# mqtt_doorbell_v2a.net
KiCad netlist of a schematic drawn in EAGLE
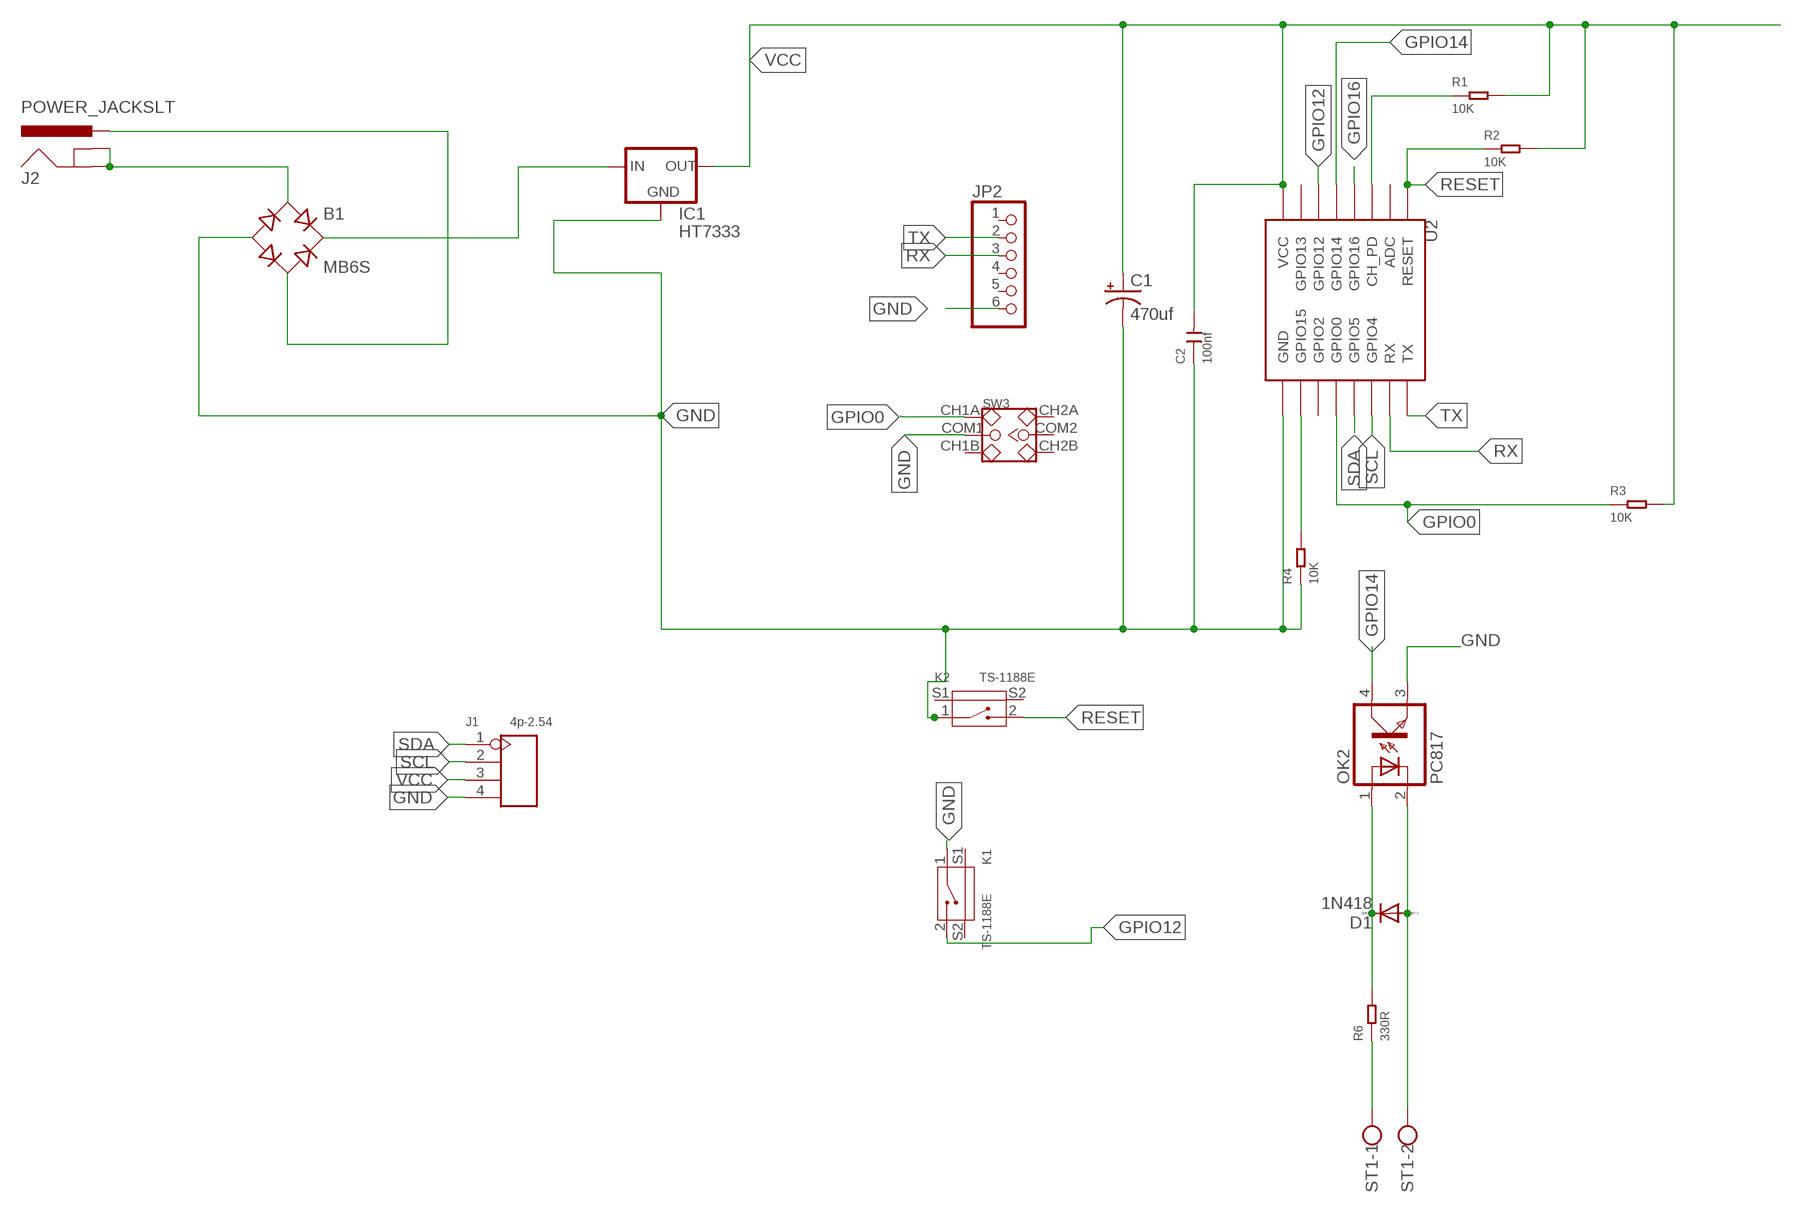
[diagram p0: schematic, sheet 1]

(export (version "E")
  (design (tool "Eeschema 10.0.6"))
  (components
    (comp (ref "B1")
      (value "MB6S")
      (footprint "eagle-import:SOIC-4")
      (libsource (lib "eagle-import") (part "MBS4"))
    )
    (comp (ref "C1")
      (value "470uf")
      (footprint "eagle-import:PANASONIC_D")
      (libsource (lib "eagle-import") (part "47UF-50V-20%(ELECT)"))
    )
    (comp (ref "C2")
      (value "100nf")
      (footprint "eagle-import:C0603")
      (fields (field (name "MPN") "CC0603KRX7R9BB104"))
      (libsource (lib "eagle-import") (part "CERAMIC-100NF-50V-10%-X7R(0603)"))
    )
    (comp (ref "D1")
      (value "1N418")
      (footprint "eagle-import:SOD-123_MINI-SMA")
      (libsource (lib "eagle-import") (part "CGRM400-G1"))
    )
    (comp (ref "IC1")
      (value "HT7333")
      (footprint "eagle-import:SOT-89")
      (libsource (lib "eagle-import") (part "HT7333"))
    )
    (comp (ref "J1")
      (value "4p-2.54")
      (footprint "eagle-import:H4-2.54")
      (fields (field (name "MPN") "F185-1104A1BSYA1"))
      (libsource (lib "eagle-import") (part "DIP-BLACK-FEMALE-HEADER-VERT(4P-2.54)"))
    )
    (comp (ref "J2")
      (value "POWER_JACKSLT")
      (footprint "eagle-import:POWER_JACK_SLOT")
      (libsource (lib "eagle-import") (part "POWER_JACKSLT"))
    )
    (comp (ref "JP2")
      (value "PINHD-1X6")
      (footprint "eagle-import:1X06")
      (libsource (lib "eagle-import") (part "PINHD-1X6"))
    )
    (comp (ref "K1")
      (value "TS-1188E")
      (footprint "eagle-import:SW4-SMD-7.0X3.5X3.5MM-90D")
      (libsource (lib "eagle-import") (part "SMD-BUTTON(2+2P-7X3.5MM-90D)"))
    )
    (comp (ref "K2")
      (value "TS-1188E")
      (footprint "eagle-import:SW4-SMD-7.0X3.5X3.5MM-90D")
      (libsource (lib "eagle-import") (part "SMD-BUTTON(2+2P-7X3.5MM-90D)"))
    )
    (comp (ref "OK2")
      (value "PC817")
      (footprint "eagle-import:SOP-4-2.54")
      (libsource (lib "eagle-import") (part "TLP181"))
    )
    (comp (ref "R1")
      (value "10K")
      (footprint "eagle-import:R0603")
      (fields (field (name "MPN") "RC0603FR-0710KL"))
      (libsource (lib "eagle-import") (part "SMD-RES-10K-1%-1/10W(0603)"))
    )
    (comp (ref "R2")
      (value "10K")
      (footprint "eagle-import:R0603")
      (fields (field (name "MPN") "RC0603FR-0710KL"))
      (libsource (lib "eagle-import") (part "SMD-RES-10K-1%-1/10W(0603)"))
    )
    (comp (ref "R3")
      (value "10K")
      (footprint "eagle-import:R0603")
      (fields (field (name "MPN") "RC0603FR-0710KL"))
      (libsource (lib "eagle-import") (part "SMD-RES-10K-1%-1/10W(0603)"))
    )
    (comp (ref "R4")
      (value "10K")
      (footprint "eagle-import:R0603")
      (fields (field (name "MPN") "RC0603FR-0710KL"))
      (libsource (lib "eagle-import") (part "SMD-RES-10K-1%-1/10W(0603)"))
    )
    (comp (ref "R6")
      (value "330R")
      (footprint "eagle-import:R0603")
      (fields (field (name "MPN") "RC0603FR-07330RL"))
      (libsource (lib "eagle-import") (part "SMD-RES-330R-1%-1/10W(0603)"))
    )
    (comp (ref "ST1")
      (value "W237-102")
      (footprint "eagle-import:W237-102")
      (fields (field (name "MPN") "237-102"))
      (libsource (lib "eagle-import") (part "W237-102"))
    )
    (comp (ref "SW3")
      (value "SMD-TOGGLE-SWITCH-2CH(2X3P-7X3.5MM)")
      (footprint "eagle-import:SW6-2.54-SMD-7.0X3.5X1.5MM")
      (libsource (lib "eagle-import") (part "SMD-TOGGLE-SWITCH-2CH(2X3P-7X3.5MM)"))
    )
    (comp (ref "U2")
      (value "ESP12SMD")
      (footprint "eagle-import:ESP12-SMD")
      (libsource (lib "eagle-import") (part "ESP12SMD"))
    )
  )
  (nets
    (net (code "1") (name "GND") (class "Default")
      (node (ref "B1") (pin "-") (pinfunction "-_-") (pintype "passive"))
      (node (ref "C1") (pin "-") (pinfunction "-_-") (pintype "passive"))
      (node (ref "C2") (pin "1") (pinfunction "1_1") (pintype "passive"))
      (node (ref "IC1") (pin "2") (pinfunction "GND_2") (pintype "input"))
      (node (ref "J1") (pin "4") (pinfunction "P$4_4") (pintype "bidirectional"))
      (node (ref "JP2") (pin "6") (pinfunction "6_6") (pintype "passive"))
      (node (ref "K1") (pin "1") (pinfunction "1_1") (pintype "bidirectional"))
      (node (ref "K2") (pin "1") (pinfunction "1_1") (pintype "bidirectional"))
      (node (ref "OK2") (pin "3") (pinfunction "EMIT_3") (pintype "passive"))
      (node (ref "R4") (pin "1") (pinfunction "1_1") (pintype "passive"))
      (node (ref "SW3") (pin "COM1") (pinfunction "COM1_COM1") (pintype "bidirectional"))
      (node (ref "U2") (pin "GND") (pinfunction "GND_GND") (pintype "bidirectional"))
    )
    (net (code "2") (name "GPIO0") (class "Default")
      (node (ref "R3") (pin "1") (pinfunction "1_1") (pintype "passive"))
      (node (ref "SW3") (pin "CH1A") (pinfunction "CH1A_CH1A") (pintype "bidirectional"))
      (node (ref "U2") (pin "GPIO0") (pinfunction "GPIO0_GPIO0") (pintype "bidirectional"))
    )
    (net (code "3") (name "GPIO12") (class "Default")
      (node (ref "K1") (pin "2") (pinfunction "2_2") (pintype "bidirectional"))
      (node (ref "U2") (pin "GPIO12") (pinfunction "GPIO12_GPIO12") (pintype "bidirectional"))
    )
    (net (code "4") (name "GPIO14") (class "Default")
      (node (ref "OK2") (pin "4") (pinfunction "COL_4") (pintype "passive"))
      (node (ref "U2") (pin "GPIO14") (pinfunction "GPIO14_GPIO14") (pintype "bidirectional"))
    )
    (net (code "5") (name "GPIO16") (class "Default")
      (node (ref "U2") (pin "GPIO16") (pinfunction "GPIO16_GPIO16") (pintype "bidirectional"))
    )
    (net (code "6") (name "Net-(B1-AC1)") (class "Default")
      (node (ref "B1") (pin "~1") (pinfunction "AC1_~1") (pintype "passive"))
      (node (ref "J2") (pin "GND@1") (pinfunction "GNDBREAK_GND@1") (pintype "bidirectional"))
      (node (ref "J2") (pin "GND@2") (pinfunction "GND_GND@2") (pintype "bidirectional"))
    )
    (net (code "7") (name "Net-(B1-AC2)") (class "Default")
      (node (ref "B1") (pin "~2") (pinfunction "AC2_~2") (pintype "passive"))
      (node (ref "J2") (pin "PWR") (pinfunction "PWR_PWR") (pintype "bidirectional"))
    )
    (net (code "8") (name "Net-(B1-Pad+)") (class "Default")
      (node (ref "B1") (pin "+") (pinfunction "+_+") (pintype "passive"))
      (node (ref "IC1") (pin "3") (pinfunction "IN_3") (pintype "input"))
      (node (ref "IC1") (pin "4") (pinfunction "IN_4") (pintype "input"))
    )
    (net (code "9") (name "Net-(OK2-A)") (class "Default")
      (node (ref "D1") (pin "C") (pinfunction "C_C") (pintype "passive"))
      (node (ref "OK2") (pin "1") (pinfunction "A_1") (pintype "passive"))
      (node (ref "R6") (pin "2") (pinfunction "2_2") (pintype "passive"))
    )
    (net (code "10") (name "Net-(OK2-C)") (class "Default")
      (node (ref "D1") (pin "A") (pinfunction "A_A") (pintype "passive"))
      (node (ref "OK2") (pin "2") (pinfunction "C_2") (pintype "passive"))
      (node (ref "ST1") (pin "2") (pinfunction "KL_2") (pintype "passive"))
    )
    (net (code "11") (name "Net-(R1-Pad1)") (class "Default")
      (node (ref "R1") (pin "1") (pinfunction "1_1") (pintype "passive"))
      (node (ref "U2") (pin "CH_PD") (pinfunction "CH_PD_CH_PD") (pintype "bidirectional"))
    )
    (net (code "12") (name "Net-(R4-Pad2)") (class "Default")
      (node (ref "R4") (pin "2") (pinfunction "2_2") (pintype "passive"))
      (node (ref "U2") (pin "GPIO15") (pinfunction "GPIO15_GPIO15") (pintype "bidirectional"))
    )
    (net (code "13") (name "Net-(ST1A-KL)") (class "Default")
      (node (ref "R6") (pin "1") (pinfunction "1_1") (pintype "passive"))
      (node (ref "ST1") (pin "1") (pinfunction "KL_1") (pintype "passive"))
    )
    (net (code "14") (name "RESET") (class "Default")
      (node (ref "K2") (pin "2") (pinfunction "2_2") (pintype "bidirectional"))
      (node (ref "R2") (pin "1") (pinfunction "1_1") (pintype "passive"))
      (node (ref "U2") (pin "RESET") (pinfunction "RESET_RESET") (pintype "bidirectional"))
    )
    (net (code "15") (name "RX") (class "Default")
      (node (ref "JP2") (pin "3") (pinfunction "3_3") (pintype "passive"))
      (node (ref "U2") (pin "RXD0") (pinfunction "RX_RXD0") (pintype "bidirectional"))
    )
    (net (code "16") (name "SCL") (class "Default")
      (node (ref "J1") (pin "2") (pinfunction "P$2_2") (pintype "bidirectional"))
      (node (ref "U2") (pin "GPIO4") (pinfunction "GPIO4_GPIO4") (pintype "bidirectional"))
    )
    (net (code "17") (name "SDA") (class "Default")
      (node (ref "J1") (pin "1") (pinfunction "P$1_1") (pintype "bidirectional"))
      (node (ref "U2") (pin "GPIO5") (pinfunction "GPIO5_GPIO5") (pintype "bidirectional"))
    )
    (net (code "18") (name "TX") (class "Default")
      (node (ref "JP2") (pin "2") (pinfunction "2_2") (pintype "passive"))
      (node (ref "U2") (pin "TXD0") (pinfunction "TX_TXD0") (pintype "bidirectional"))
    )
    (net (code "19") (name "VCC") (class "Default")
      (node (ref "C1") (pin "+") (pinfunction "+_+") (pintype "passive"))
      (node (ref "C2") (pin "2") (pinfunction "2_2") (pintype "passive"))
      (node (ref "IC1") (pin "1") (pinfunction "OUT_1") (pintype "passive"))
      (node (ref "J1") (pin "3") (pinfunction "P$3_3") (pintype "bidirectional"))
      (node (ref "R1") (pin "2") (pinfunction "2_2") (pintype "passive"))
      (node (ref "R2") (pin "2") (pinfunction "2_2") (pintype "passive"))
      (node (ref "R3") (pin "2") (pinfunction "2_2") (pintype "passive"))
      (node (ref "U2") (pin "VCC") (pinfunction "VCC_VCC") (pintype "bidirectional"))
    )
    (net (code "20") (name "unconnected-(JP2-Pad1)") (class "Default")
      (node (ref "JP2") (pin "1") (pinfunction "1_1") (pintype "passive"))
    )
    (net (code "21") (name "unconnected-(JP2-Pad4)") (class "Default")
      (node (ref "JP2") (pin "4") (pinfunction "4_4") (pintype "passive"))
    )
    (net (code "22") (name "unconnected-(JP2-Pad5)") (class "Default")
      (node (ref "JP2") (pin "5") (pinfunction "5_5") (pintype "passive"))
    )
    (net (code "23") (name "unconnected-(K1-PadS1)") (class "Default")
      (node (ref "K1") (pin "S1") (pinfunction "S1_S1") (pintype "bidirectional"))
    )
    (net (code "24") (name "unconnected-(K1-PadS2)") (class "Default")
      (node (ref "K1") (pin "S2") (pinfunction "S2_S2") (pintype "bidirectional"))
    )
    (net (code "25") (name "unconnected-(K2-PadS1)") (class "Default")
      (node (ref "K2") (pin "S1") (pinfunction "S1_S1") (pintype "bidirectional"))
    )
    (net (code "26") (name "unconnected-(K2-PadS2)") (class "Default")
      (node (ref "K2") (pin "S2") (pinfunction "S2_S2") (pintype "bidirectional"))
    )
    (net (code "27") (name "unconnected-(SW3-PadCH1B)") (class "Default")
      (node (ref "SW3") (pin "CH1B") (pinfunction "CH1B_CH1B") (pintype "bidirectional"))
    )
    (net (code "28") (name "unconnected-(SW3-PadCH2A)") (class "Default")
      (node (ref "SW3") (pin "CH2A") (pinfunction "CH2A_CH2A") (pintype "bidirectional"))
    )
    (net (code "29") (name "unconnected-(SW3-PadCH2B)") (class "Default")
      (node (ref "SW3") (pin "CH2B") (pinfunction "CH2B_CH2B") (pintype "bidirectional"))
    )
    (net (code "30") (name "unconnected-(SW3-PadCOM2)") (class "Default")
      (node (ref "SW3") (pin "COM2") (pinfunction "COM2_COM2") (pintype "bidirectional"))
    )
    (net (code "31") (name "unconnected-(U2-PadADC)") (class "Default")
      (node (ref "U2") (pin "ADC") (pinfunction "ADC_ADC") (pintype "bidirectional"))
    )
    (net (code "32") (name "unconnected-(U2-PadGPIO2)") (class "Default")
      (node (ref "U2") (pin "GPIO2") (pinfunction "GPIO2_GPIO2") (pintype "bidirectional"))
    )
    (net (code "33") (name "unconnected-(U2-PadGPIO13)") (class "Default")
      (node (ref "U2") (pin "GPIO13") (pinfunction "GPIO13_GPIO13") (pintype "bidirectional"))
    )
  )
)
